# Sheet3.net
KiCad netlist of a schematic drawn in Altium Designer
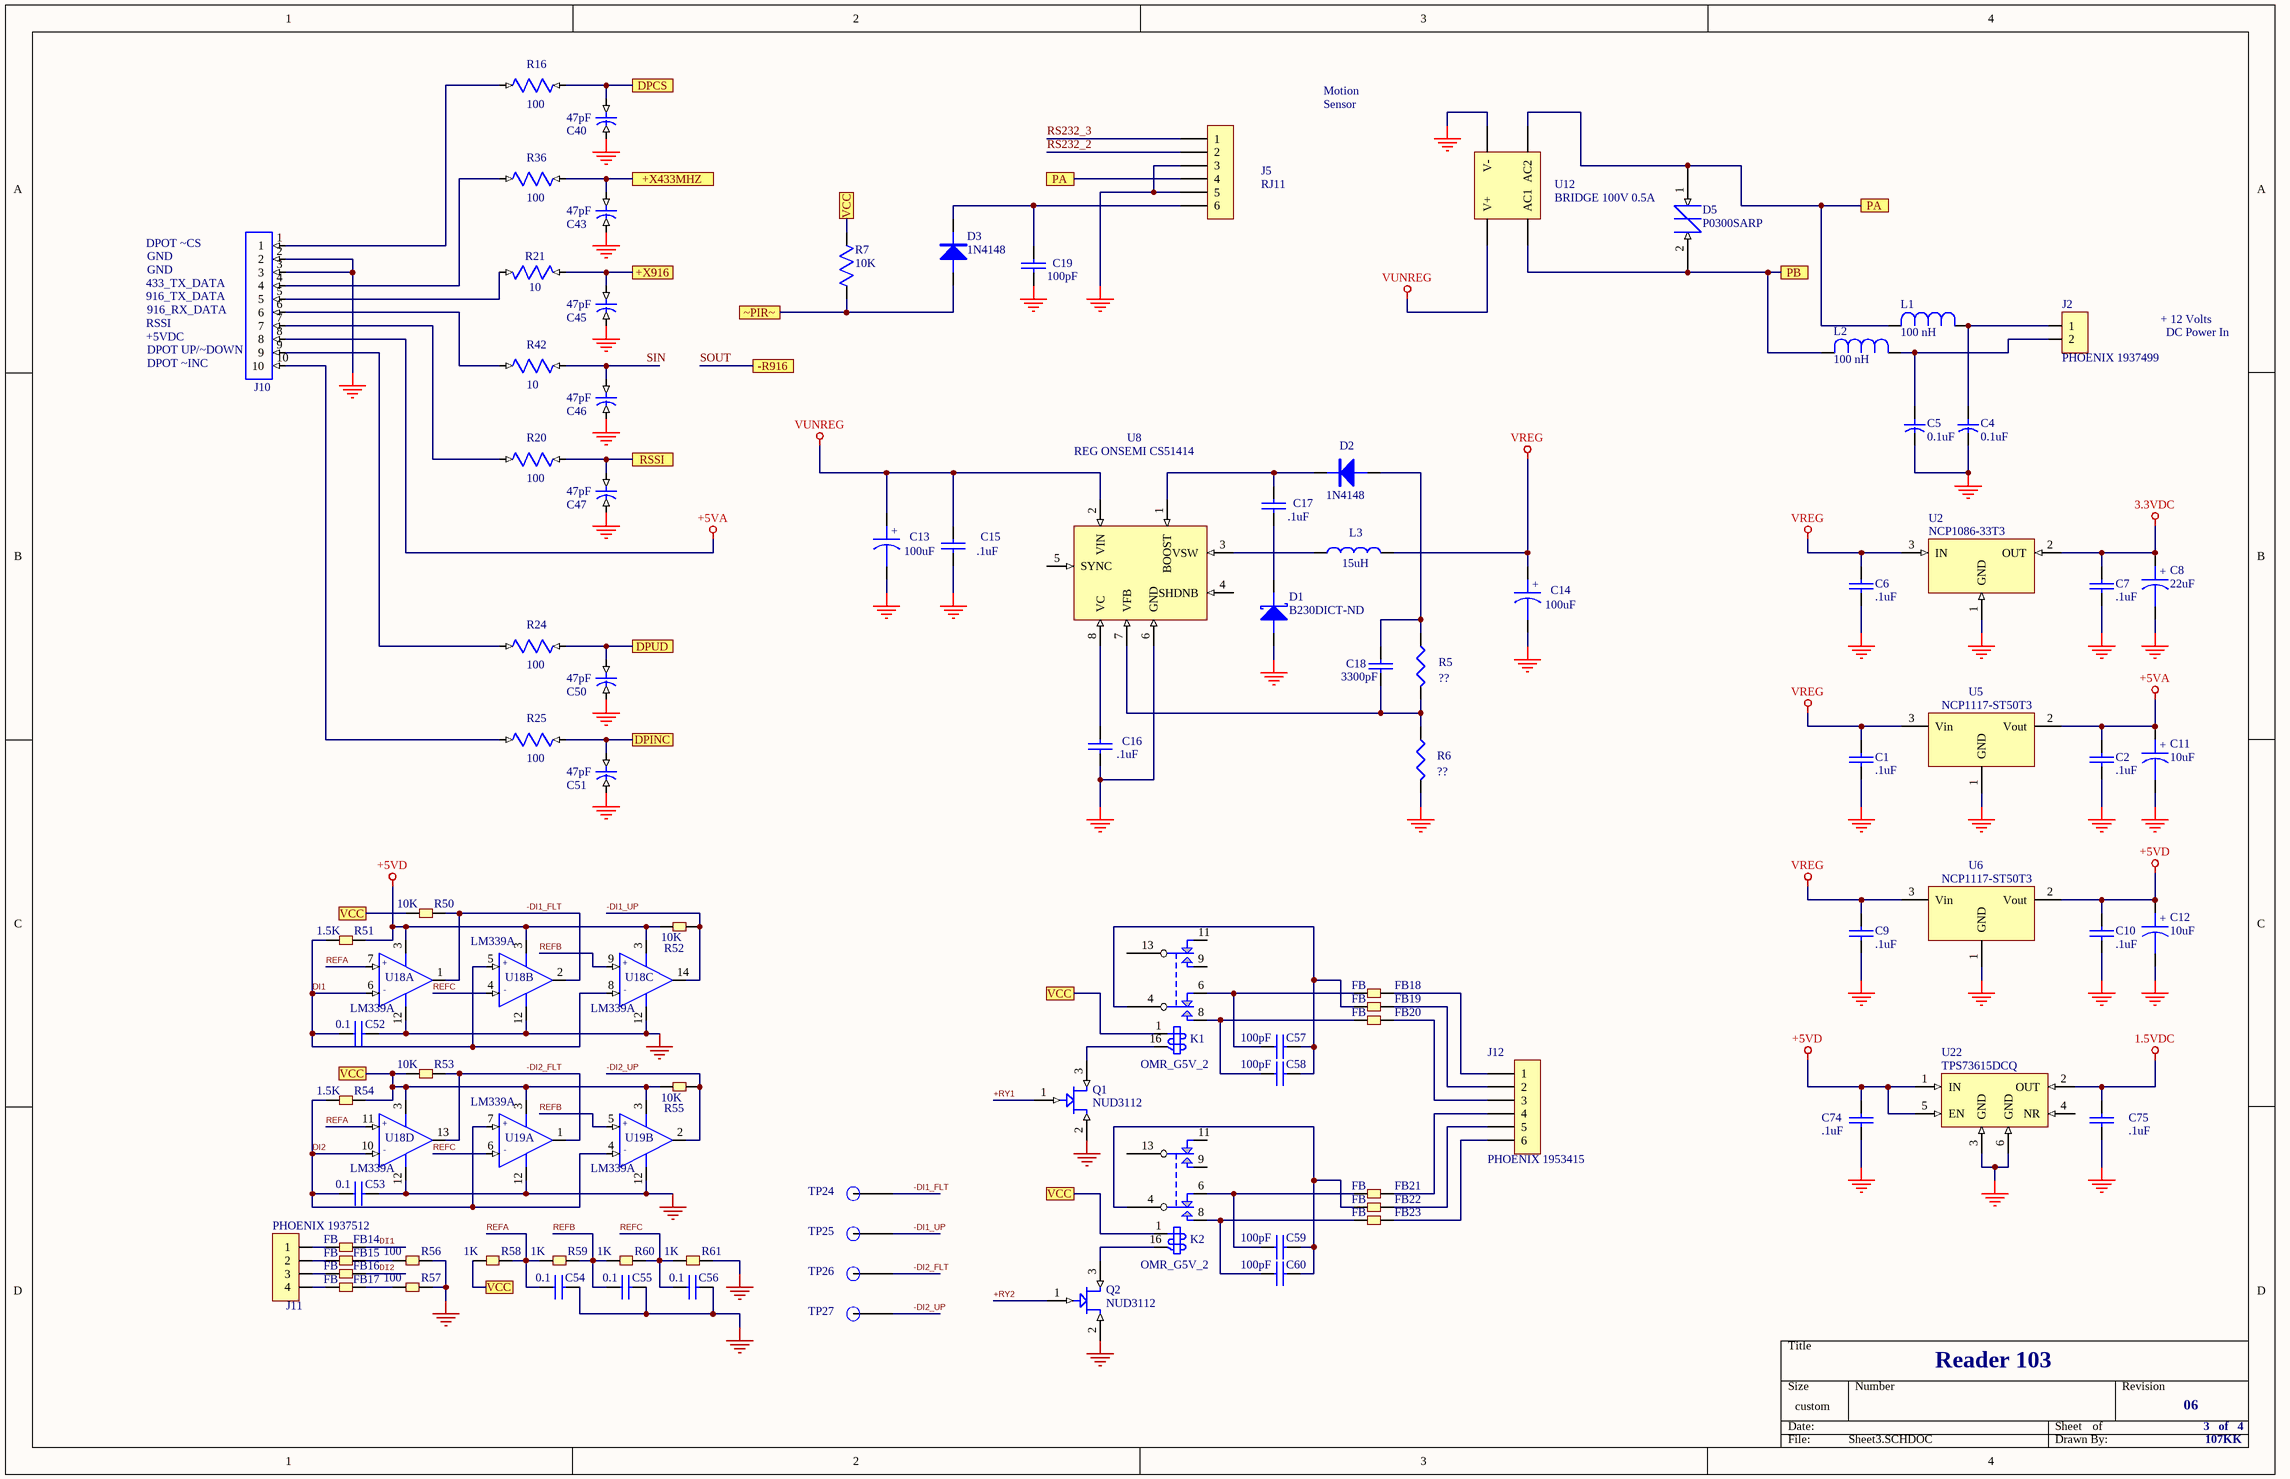
[diagram p0: Sheet3.SCHDOC]

(export (version "E")
  (design (tool "Eeschema 10.0.6"))
  (components
    (comp (ref "C1")
      (value ".1uF")
      (footprint "0603")
      (description "Capacitor")
      (libsource (lib "*") (part "CAP"))
    )
    (comp (ref "C2")
      (value ".1uF")
      (footprint "0603")
      (description "Capacitor")
      (libsource (lib "*") (part "CAP"))
    )
    (comp (ref "C4") (value "0.1uF") (footprint "0603") (libsource (lib "*") (part "C_0603")))
    (comp (ref "C5") (value "0.1uF") (footprint "0603") (libsource (lib "*") (part "C_0603")))
    (comp (ref "C6")
      (value ".1uF")
      (footprint "0603")
      (description "Capacitor")
      (libsource (lib "*") (part "CAP"))
    )
    (comp (ref "C7")
      (value ".1uF")
      (footprint "0603")
      (description "Capacitor")
      (libsource (lib "*") (part "CAP"))
    )
    (comp (ref "C8")
      (value "22uF")
      (footprint "CAP A CASE")
      (description "Capacitor")
      (libsource (lib "*") (part "CAPACITOR POL"))
    )
    (comp (ref "C9")
      (value ".1uF")
      (footprint "0603")
      (description "Capacitor")
      (libsource (lib "*") (part "CAP"))
    )
    (comp (ref "C10")
      (value ".1uF")
      (footprint "0603")
      (description "Capacitor")
      (libsource (lib "*") (part "CAP"))
    )
    (comp (ref "C11")
      (value "10uF")
      (footprint "CAP A CASE")
      (description "Capacitor")
      (libsource (lib "*") (part "CAPACITOR POL"))
    )
    (comp (ref "C12")
      (value "10uF")
      (footprint "CAP A CASE")
      (description "Capacitor")
      (libsource (lib "*") (part "CAPACITOR POL"))
    )
    (comp (ref "C13")
      (value "100uF")
      (footprint "CAP D CASE")
      (description "Capacitor")
      (libsource (lib "*") (part "CAPACITOR POL"))
    )
    (comp (ref "C14")
      (value "100uF")
      (footprint "CAP D CASE")
      (description "Capacitor")
      (libsource (lib "*") (part "CAPACITOR POL"))
    )
    (comp (ref "C15")
      (value ".1uF")
      (footprint "0603")
      (description "Capacitor")
      (libsource (lib "*") (part "CAP"))
    )
    (comp (ref "C16")
      (value ".1uF")
      (footprint "0603")
      (description "Capacitor")
      (libsource (lib "*") (part "CAP"))
    )
    (comp (ref "C17")
      (value ".1uF")
      (footprint "0603")
      (description "Capacitor")
      (libsource (lib "*") (part "CAP"))
    )
    (comp (ref "C18")
      (value "3300pF")
      (footprint "0603")
      (description "Capacitor")
      (libsource (lib "*") (part "CAP"))
    )
    (comp (ref "C19")
      (value "100pF")
      (footprint "0603")
      (description "Capacitor")
      (libsource (lib "*") (part "CAP"))
    )
    (comp (ref "C40") (value "47pF") (footprint "C0603") (libsource (lib "*") (part "C0603")))
    (comp (ref "C43") (value "47pF") (footprint "C0603") (libsource (lib "*") (part "C0603")))
    (comp (ref "C45") (value "47pF") (footprint "C0603") (libsource (lib "*") (part "C0603")))
    (comp (ref "C46") (value "47pF") (footprint "C0603") (libsource (lib "*") (part "C0603")))
    (comp (ref "C47") (value "47pF") (footprint "C0603") (libsource (lib "*") (part "C0603")))
    (comp (ref "C50") (value "47pF") (footprint "C0603") (libsource (lib "*") (part "C0603")))
    (comp (ref "C51") (value "47pF") (footprint "C0603") (libsource (lib "*") (part "C0603")))
    (comp (ref "C52") (value "0.1") (footprint "0805") (libsource (lib "*") (part "CAP NP_1")))
    (comp (ref "C53") (value "0.1") (footprint "0805") (libsource (lib "*") (part "CAP NP_1")))
    (comp (ref "C54") (value "0.1") (footprint "0805") (libsource (lib "*") (part "CAP NP_1")))
    (comp (ref "C55") (value "0.1") (footprint "0805") (libsource (lib "*") (part "CAP NP_1")))
    (comp (ref "C56") (value "0.1") (footprint "0805") (libsource (lib "*") (part "CAP NP_1")))
    (comp (ref "C57") (value "100pF") (footprint "SM/C_0805") (libsource (lib "*") (part "CAP NP_1")))
    (comp (ref "C58") (value "100pF") (footprint "SM/C_0805") (libsource (lib "*") (part "CAP NP_1")))
    (comp (ref "C59") (value "100pF") (footprint "SM/C_0805") (libsource (lib "*") (part "CAP NP_1")))
    (comp (ref "C60") (value "100pF") (footprint "SM/C_0805") (libsource (lib "*") (part "CAP NP_1")))
    (comp (ref "C74")
      (value ".1uF")
      (footprint "0603")
      (description "Capacitor")
      (libsource (lib "*") (part "CAP"))
    )
    (comp (ref "C75")
      (value ".1uF")
      (footprint "0603")
      (description "Capacitor")
      (libsource (lib "*") (part "CAP"))
    )
    (comp (ref "D1")
      (value "B230DICT-ND")
      (footprint "DIODE SMB")
      (description "Schottky Diode")
      (libsource (lib "*") (part "DIODE SCHOTTKY"))
    )
    (comp (ref "D2")
      (value "1N4148")
      (footprint "SOD123")
      (description "Diode")
      (libsource (lib "*") (part "DIODE"))
    )
    (comp (ref "D3")
      (value "1N4148")
      (footprint "SOD123")
      (description "Diode")
      (libsource (lib "*") (part "DIODE"))
    )
    (comp (ref "D5") (value "P0300SARP") (footprint "TRANSORB_1") (libsource (lib "*") (part "TRANSORB")))
    (comp (ref "FB14") (value "FB") (footprint "0603") (libsource (lib "*") (part "FB")))
    (comp (ref "FB15") (value "FB") (footprint "0603") (libsource (lib "*") (part "FB")))
    (comp (ref "FB16") (value "FB") (footprint "0603") (libsource (lib "*") (part "FB")))
    (comp (ref "FB17") (value "FB") (footprint "0603") (libsource (lib "*") (part "FB")))
    (comp (ref "FB18") (value "FB") (footprint "SM/R_1206") (libsource (lib "*") (part "FB")))
    (comp (ref "FB19") (value "FB") (footprint "SM/R_1206") (libsource (lib "*") (part "FB")))
    (comp (ref "FB20") (value "FB") (footprint "SM/R_1206") (libsource (lib "*") (part "FB")))
    (comp (ref "FB21") (value "FB") (footprint "SM/R_1206") (libsource (lib "*") (part "FB")))
    (comp (ref "FB22") (value "FB") (footprint "SM/R_1206") (libsource (lib "*") (part "FB")))
    (comp (ref "FB23") (value "FB") (footprint "SM/R_1206") (libsource (lib "*") (part "FB")))
    (comp (ref "J2")
      (value "PHOENIX 1937499")
      (footprint "CONN PHOENIX 1803227-2")
      (description "Connector")
      (libsource (lib "*") (part "CON2"))
    )
    (comp (ref "J5")
      (value "RJ11")
      (footprint "RJ11")
      (description "Connector")
      (libsource (lib "*") (part "CON6"))
    )
    (comp (ref "J10") (value "1X10 HEADER") (footprint "1X10 HEADER") (libsource (lib "*") (part "HDR10")))
    (comp (ref "J11")
      (value "PHOENIX 1937512")
      (footprint "CONN PHOENIX 1803293-4")
      (libsource (lib "*") (part "CON4"))
    )
    (comp (ref "J12")
      (value "PHOENIX 1953415")
      (footprint "CONN PHOENIX 1953211-6")
      (description "Connector")
      (libsource (lib "*") (part "CON6"))
    )
    (comp (ref "K1") (value "OMR_G5V_2") (footprint "RELAY44") (libsource (lib "*") (part "OMRON_G5V_3")))
    (comp (ref "K2") (value "OMR_G5V_2") (footprint "RELAY44") (libsource (lib "*") (part "OMRON_G5V_3")))
    (comp (ref "L1") (value "100 nH") (footprint "0603") (libsource (lib "*") (part "INDUCTOR_1")))
    (comp (ref "L2") (value "100 nH") (footprint "0603") (libsource (lib "*") (part "INDUCTOR_1")))
    (comp (ref "L3")
      (value "15uH")
      (footprint "COIL COILTRONICS UP2B-150")
      (libsource (lib "*") (part "INDUCTOR1"))
    )
    (comp (ref "Q1")
      (value "NUD3112")
      (footprint "SOT23")
      (libsource (lib "*") (part "INDUCTIVE LOAD DRIVER"))
    )
    (comp (ref "Q2")
      (value "NUD3112")
      (footprint "SOT23")
      (libsource (lib "*") (part "INDUCTIVE LOAD DRIVER"))
    )
    (comp (ref "R5") (value "??") (footprint "0603") (libsource (lib "*") (part "RES1")))
    (comp (ref "R6") (value "??") (footprint "0603") (libsource (lib "*") (part "RES1")))
    (comp (ref "R7") (value "10K") (footprint "0603") (libsource (lib "*") (part "R_0603")))
    (comp (ref "R16") (value "100") (footprint "R0603") (libsource (lib "*") (part "R0603")))
    (comp (ref "R20") (value "100") (footprint "R0603") (libsource (lib "*") (part "R0603")))
    (comp (ref "R21") (value "10") (footprint "R-603") (libsource (lib "*") (part "R_603")))
    (comp (ref "R24") (value "100") (footprint "R0603") (libsource (lib "*") (part "R0603")))
    (comp (ref "R25") (value "100") (footprint "R0603") (libsource (lib "*") (part "R0603")))
    (comp (ref "R36") (value "100") (footprint "R0603") (libsource (lib "*") (part "R0603")))
    (comp (ref "R42") (value "10") (footprint "R0603") (libsource (lib "*") (part "R0603")))
    (comp (ref "R50") (value "10K") (footprint "0805") (libsource (lib "*") (part "RS")))
    (comp (ref "R51") (value "1.5K") (footprint "0805") (libsource (lib "*") (part "RS")))
    (comp (ref "R52") (value "10K") (footprint "0805") (libsource (lib "*") (part "RS")))
    (comp (ref "R53") (value "10K") (footprint "0805") (libsource (lib "*") (part "RS")))
    (comp (ref "R54") (value "1.5K") (footprint "0805") (libsource (lib "*") (part "RS")))
    (comp (ref "R55") (value "10K") (footprint "0805") (libsource (lib "*") (part "RS")))
    (comp (ref "R56") (value "100") (footprint "0805") (libsource (lib "*") (part "RS")))
    (comp (ref "R57") (value "100") (footprint "0805") (libsource (lib "*") (part "RS")))
    (comp (ref "R58") (value "1K") (footprint "0805") (libsource (lib "*") (part "RS")))
    (comp (ref "R59") (value "1K") (footprint "0805") (libsource (lib "*") (part "RS")))
    (comp (ref "R60") (value "1K") (footprint "0805") (libsource (lib "*") (part "RS")))
    (comp (ref "R61") (value "1K") (footprint "0805") (libsource (lib "*") (part "RS")))
    (comp (ref "TP24") (value "TP") (footprint "TESTPOINT-1") (libsource (lib "*") (part "TESTPOINT_1")))
    (comp (ref "TP25") (value "TP") (footprint "TESTPOINT-1") (libsource (lib "*") (part "TESTPOINT_1")))
    (comp (ref "TP26") (value "TP") (footprint "TESTPOINT-1") (libsource (lib "*") (part "TESTPOINT_1")))
    (comp (ref "TP27") (value "TP") (footprint "TESTPOINT-1") (libsource (lib "*") (part "TESTPOINT_1")))
    (comp (ref "U2")
      (value "NCP1086-33T3")
      (footprint "SOT223 REG GOI")
      (libsource (lib "*") (part "REG GOI"))
    )
    (comp (ref "U5")
      (value "NCP1117-ST50T3")
      (footprint "SOT223 REG")
      (libsource (lib "*") (part "REG REVERSED"))
    )
    (comp (ref "U6")
      (value "NCP1117-ST50T3")
      (footprint "SOT223 REG")
      (libsource (lib "*") (part "REG REVERSED"))
    )
    (comp (ref "U8")
      (value "REG ONSEMI CS51414")
      (footprint "SO8")
      (libsource (lib "*") (part "REG ONSEMI CS51414"))
    )
    (comp (ref "U12")
      (value "BRIDGE 100V 0.5A")
      (footprint "BRIDGE")
      (description "Diode Bridge")
      (libsource (lib "*") (part "BRIDGE2"))
    )
    (comp (ref "U18") (value "LM339A") (footprint "SO14") (libsource (lib "*") (part "LM339")))
    (comp (ref "U19") (value "LM339A") (footprint "SO14") (libsource (lib "*") (part "LM339")))
    (comp (ref "U22")
      (value "TPS73615DCQ")
      (footprint "SOT223-5")
      (libsource (lib "*") (part "REG SOT223-5"))
    )
  )
  (nets
    (net (code "1") (name "+5VA") (class "Default")
      (node (ref "C11") (pin "1") (pinfunction "1_1") (pintype "passive"))
      (node (ref "C2") (pin "1") (pinfunction "1_1") (pintype "passive"))
      (node (ref "J10") (pin "8") (pinfunction "8_8") (pintype "input"))
      (node (ref "U5") (pin "2") (pinfunction "Vout_2") (pintype "passive"))
    )
    (net (code "2") (name "+5VD") (class "Default")
      (node (ref "C10") (pin "1") (pinfunction "1_1") (pintype "passive"))
      (node (ref "C12") (pin "1") (pinfunction "1_1") (pintype "passive"))
      (node (ref "C74") (pin "1") (pinfunction "1_1") (pintype "passive"))
      (node (ref "R51") (pin "1") (pinfunction "1_1") (pintype "passive"))
      (node (ref "R52") (pin "2") (pinfunction "2_2") (pintype "passive"))
      (node (ref "U18") (pin "3") (pinfunction "V+_3") (pintype "power_in"))
      (node (ref "U22") (pin "1") (pinfunction "IN_1") (pintype "input"))
      (node (ref "U22") (pin "5") (pinfunction "EN_5") (pintype "input"))
      (node (ref "U6") (pin "2") (pinfunction "Vout_2") (pintype "passive"))
    )
    (net (code "3") (name "/+RY1") (class "Default")
      (node (ref "Q1") (pin "1") (pinfunction "G_1") (pintype "input"))
    )
    (net (code "4") (name "/+RY2") (class "Default")
      (node (ref "Q2") (pin "1") (pinfunction "G_1") (pintype "input"))
    )
    (net (code "5") (name "/+X433MHZ") (class "Default")
      (node (ref "C43") (pin "1") (pinfunction "A_1") (pintype "input"))
      (node (ref "R36") (pin "2") (pinfunction "B_2") (pintype "input"))
    )
    (net (code "6") (name "/+X916") (class "Default")
      (node (ref "C45") (pin "1") (pinfunction "A_1") (pintype "input"))
      (node (ref "R21") (pin "1") (pinfunction "A_1") (pintype "input"))
    )
    (net (code "7") (name "/-DI1_FLT") (class "Default")
      (node (ref "R50") (pin "1") (pinfunction "1_1") (pintype "passive"))
      (node (ref "TP24") (pin "1") (pinfunction "TP_1") (pintype "passive"))
      (node (ref "U18") (pin "1") (pinfunction "OUT_1") (pintype "open_collector"))
      (node (ref "U18") (pin "2") (pinfunction "OUT_2") (pintype "open_collector"))
    )
    (net (code "8") (name "/-DI1_UP") (class "Default")
      (node (ref "R52") (pin "1") (pinfunction "1_1") (pintype "passive"))
      (node (ref "TP25") (pin "1") (pinfunction "TP_1") (pintype "passive"))
      (node (ref "U18") (pin "14") (pinfunction "OUT_14") (pintype "open_collector"))
    )
    (net (code "9") (name "/-DI2_FLT") (class "Default")
      (node (ref "R53") (pin "1") (pinfunction "1_1") (pintype "passive"))
      (node (ref "TP26") (pin "1") (pinfunction "TP_1") (pintype "passive"))
      (node (ref "U18") (pin "13") (pinfunction "OUT_13") (pintype "open_collector"))
      (node (ref "U19") (pin "1") (pinfunction "OUT_1") (pintype "open_collector"))
    )
    (net (code "10") (name "/-DI2_UP") (class "Default")
      (node (ref "R55") (pin "1") (pinfunction "1_1") (pintype "passive"))
      (node (ref "TP27") (pin "1") (pinfunction "TP_1") (pintype "passive"))
      (node (ref "U19") (pin "2") (pinfunction "OUT_2") (pintype "open_collector"))
    )
    (net (code "11") (name "/DI1") (class "Default")
      (node (ref "C52") (pin "1") (pinfunction "1_1") (pintype "passive"))
      (node (ref "FB14") (pin "1") (pinfunction "1_1") (pintype "passive"))
      (node (ref "R51") (pin "2") (pinfunction "2_2") (pintype "passive"))
      (node (ref "U18") (pin "5") (pinfunction "+_5") (pintype "input"))
      (node (ref "U18") (pin "6") (pinfunction "-_6") (pintype "input"))
      (node (ref "U18") (pin "8") (pinfunction "-_8") (pintype "input"))
    )
    (net (code "12") (name "/DI2") (class "Default")
      (node (ref "C53") (pin "1") (pinfunction "1_1") (pintype "passive"))
      (node (ref "FB16") (pin "1") (pinfunction "1_1") (pintype "passive"))
      (node (ref "R54") (pin "2") (pinfunction "2_2") (pintype "passive"))
      (node (ref "U18") (pin "10") (pinfunction "-_10") (pintype "input"))
      (node (ref "U19") (pin "4") (pinfunction "-_4") (pintype "input"))
      (node (ref "U19") (pin "7") (pinfunction "+_7") (pintype "input"))
    )
    (net (code "13") (name "/DPCS") (class "Default")
      (node (ref "C40") (pin "1") (pinfunction "A_1") (pintype "input"))
      (node (ref "R16") (pin "2") (pinfunction "B_2") (pintype "input"))
    )
    (net (code "14") (name "/DPINC") (class "Default")
      (node (ref "C51") (pin "1") (pinfunction "A_1") (pintype "input"))
      (node (ref "R25") (pin "2") (pinfunction "B_2") (pintype "input"))
    )
    (net (code "15") (name "/DPUD") (class "Default")
      (node (ref "C50") (pin "1") (pinfunction "A_1") (pintype "input"))
      (node (ref "R24") (pin "2") (pinfunction "B_2") (pintype "input"))
    )
    (net (code "16") (name "/PA") (class "Default")
      (node (ref "D5") (pin "1") (pinfunction "1_1") (pintype "input"))
      (node (ref "J5") (pin "4") (pinfunction "4_4") (pintype "passive"))
      (node (ref "L1") (pin "1") (pinfunction "B_1") (pintype "passive"))
      (node (ref "U12") (pin "AC2") (pinfunction "AC2_AC2") (pintype "passive"))
    )
    (net (code "17") (name "/PB") (class "Default")
      (node (ref "D5") (pin "2") (pinfunction "2_2") (pintype "input"))
      (node (ref "L2") (pin "1") (pinfunction "B_1") (pintype "passive"))
      (node (ref "U12") (pin "AC1") (pinfunction "AC1_AC1") (pintype "passive"))
    )
    (net (code "18") (name "/REFA") (class "Default")
      (node (ref "C54") (pin "1") (pinfunction "1_1") (pintype "passive"))
      (node (ref "R58") (pin "1") (pinfunction "1_1") (pintype "passive"))
      (node (ref "R59") (pin "2") (pinfunction "2_2") (pintype "passive"))
      (node (ref "U18") (pin "11") (pinfunction "+_11") (pintype "input"))
      (node (ref "U18") (pin "7") (pinfunction "+_7") (pintype "input"))
    )
    (net (code "19") (name "/REFB") (class "Default")
      (node (ref "C55") (pin "1") (pinfunction "1_1") (pintype "passive"))
      (node (ref "R59") (pin "1") (pinfunction "1_1") (pintype "passive"))
      (node (ref "R60") (pin "2") (pinfunction "2_2") (pintype "passive"))
      (node (ref "U18") (pin "9") (pinfunction "+_9") (pintype "input"))
      (node (ref "U19") (pin "5") (pinfunction "+_5") (pintype "input"))
    )
    (net (code "20") (name "/REFC") (class "Default")
      (node (ref "C56") (pin "1") (pinfunction "1_1") (pintype "passive"))
      (node (ref "R60") (pin "1") (pinfunction "1_1") (pintype "passive"))
      (node (ref "R61") (pin "2") (pinfunction "2_2") (pintype "passive"))
      (node (ref "U18") (pin "4") (pinfunction "-_4") (pintype "input"))
      (node (ref "U19") (pin "6") (pinfunction "-_6") (pintype "input"))
    )
    (net (code "21") (name "/RS232_2") (class "Default")
      (node (ref "J5") (pin "2") (pinfunction "2_2") (pintype "passive"))
    )
    (net (code "22") (name "/RS232_3") (class "Default")
      (node (ref "J5") (pin "1") (pinfunction "1_1") (pintype "passive"))
    )
    (net (code "23") (name "/RSSI") (class "Default")
      (node (ref "C47") (pin "1") (pinfunction "A_1") (pintype "input"))
      (node (ref "R20") (pin "2") (pinfunction "B_2") (pintype "input"))
    )
    (net (code "24") (name "/SIN") (class "Default")
      (node (ref "C46") (pin "1") (pinfunction "A_1") (pintype "input"))
      (node (ref "R42") (pin "2") (pinfunction "B_2") (pintype "input"))
    )
    (net (code "26") (name "/VCC") (class "Default")
      (node (ref "K1") (pin "1") (pinfunction "COIL1_1") (pintype "passive"))
      (node (ref "K2") (pin "1") (pinfunction "COIL1_1") (pintype "passive"))
      (node (ref "R50") (pin "2") (pinfunction "2_2") (pintype "passive"))
      (node (ref "R53") (pin "2") (pinfunction "2_2") (pintype "passive"))
      (node (ref "R54") (pin "1") (pinfunction "1_1") (pintype "passive"))
      (node (ref "R55") (pin "2") (pinfunction "2_2") (pintype "passive"))
      (node (ref "R58") (pin "2") (pinfunction "2_2") (pintype "passive"))
      (node (ref "R7") (pin "1") (pinfunction "A_1") (pintype "passive"))
      (node (ref "U18") (pin "3") (pinfunction "V+_3") (pintype "power_in"))
      (node (ref "U19") (pin "3") (pinfunction "V+_3") (pintype "power_in"))
    )
    (net (code "27") (name "/~PIR~") (class "Default")
      (node (ref "D3") (pin "A") (pinfunction "A_A") (pintype "passive"))
      (node (ref "R7") (pin "2") (pinfunction "B_2") (pintype "passive"))
    )
    (net (code "28") (name "1.5VDC") (class "Default")
      (node (ref "C75") (pin "1") (pinfunction "1_1") (pintype "passive"))
      (node (ref "U22") (pin "2") (pinfunction "OUT_2") (pintype "input"))
    )
    (net (code "29") (name "3.3VDC") (class "Default")
      (node (ref "C7") (pin "1") (pinfunction "1_1") (pintype "passive"))
      (node (ref "C8") (pin "1") (pinfunction "1_1") (pintype "passive"))
      (node (ref "U2") (pin "2") (pinfunction "OUT_2") (pintype "input"))
    )
    (net (code "30") (name "GND_COM") (class "Default")
      (node (ref "C1") (pin "2") (pinfunction "2_2") (pintype "passive"))
      (node (ref "C10") (pin "2") (pinfunction "2_2") (pintype "passive"))
      (node (ref "C11") (pin "2") (pinfunction "2_2") (pintype "passive"))
      (node (ref "C12") (pin "2") (pinfunction "2_2") (pintype "passive"))
      (node (ref "C13") (pin "2") (pinfunction "2_2") (pintype "passive"))
      (node (ref "C14") (pin "2") (pinfunction "2_2") (pintype "passive"))
      (node (ref "C15") (pin "2") (pinfunction "2_2") (pintype "passive"))
      (node (ref "C16") (pin "2") (pinfunction "2_2") (pintype "passive"))
      (node (ref "C19") (pin "2") (pinfunction "2_2") (pintype "passive"))
      (node (ref "C2") (pin "2") (pinfunction "2_2") (pintype "passive"))
      (node (ref "C4") (pin "2") (pinfunction "B_2") (pintype "passive"))
      (node (ref "C40") (pin "2") (pinfunction "B_2") (pintype "input"))
      (node (ref "C43") (pin "2") (pinfunction "B_2") (pintype "input"))
      (node (ref "C45") (pin "2") (pinfunction "B_2") (pintype "input"))
      (node (ref "C46") (pin "2") (pinfunction "B_2") (pintype "input"))
      (node (ref "C47") (pin "2") (pinfunction "B_2") (pintype "input"))
      (node (ref "C5") (pin "2") (pinfunction "B_2") (pintype "passive"))
      (node (ref "C50") (pin "2") (pinfunction "B_2") (pintype "input"))
      (node (ref "C51") (pin "2") (pinfunction "B_2") (pintype "input"))
      (node (ref "C52") (pin "2") (pinfunction "2_2") (pintype "passive"))
      (node (ref "C53") (pin "2") (pinfunction "2_2") (pintype "passive"))
      (node (ref "C54") (pin "2") (pinfunction "2_2") (pintype "passive"))
      (node (ref "C55") (pin "2") (pinfunction "2_2") (pintype "passive"))
      (node (ref "C56") (pin "2") (pinfunction "2_2") (pintype "passive"))
      (node (ref "C6") (pin "2") (pinfunction "2_2") (pintype "passive"))
      (node (ref "C7") (pin "2") (pinfunction "2_2") (pintype "passive"))
      (node (ref "C74") (pin "2") (pinfunction "2_2") (pintype "passive"))
      (node (ref "C75") (pin "2") (pinfunction "2_2") (pintype "passive"))
      (node (ref "C8") (pin "2") (pinfunction "2_2") (pintype "passive"))
      (node (ref "C9") (pin "2") (pinfunction "2_2") (pintype "passive"))
      (node (ref "D1") (pin "A") (pinfunction "A_A") (pintype "passive"))
      (node (ref "J10") (pin "2") (pinfunction "2_2") (pintype "input"))
      (node (ref "J10") (pin "3") (pinfunction "3_3") (pintype "input"))
      (node (ref "J5") (pin "3") (pinfunction "3_3") (pintype "passive"))
      (node (ref "J5") (pin "5") (pinfunction "5_5") (pintype "passive"))
      (node (ref "Q1") (pin "2") (pinfunction "S_2") (pintype "input"))
      (node (ref "Q2") (pin "2") (pinfunction "S_2") (pintype "input"))
      (node (ref "R56") (pin "1") (pinfunction "1_1") (pintype "passive"))
      (node (ref "R57") (pin "1") (pinfunction "1_1") (pintype "passive"))
      (node (ref "R6") (pin "2") (pinfunction "2_2") (pintype "passive"))
      (node (ref "R61") (pin "1") (pinfunction "1_1") (pintype "passive"))
      (node (ref "U12") (pin "V-") (pinfunction "V-_V-") (pintype "passive"))
      (node (ref "U18") (pin "12") (pinfunction "V-_12") (pintype "power_in"))
      (node (ref "U19") (pin "12") (pinfunction "V-_12") (pintype "power_in"))
      (node (ref "U2") (pin "1") (pinfunction "GND_1") (pintype "input"))
      (node (ref "U22") (pin "3") (pinfunction "GND_3") (pintype "input"))
      (node (ref "U22") (pin "6") (pinfunction "GND_6") (pintype "input"))
      (node (ref "U5") (pin "1") (pinfunction "GND_1") (pintype "passive"))
      (node (ref "U6") (pin "1") (pinfunction "GND_1") (pintype "passive"))
      (node (ref "U8") (pin "6") (pinfunction "GND_6") (pintype "input"))
    )
    (net (code "31") (name "Net-(C4-A)") (class "Default")
      (node (ref "C4") (pin "1") (pinfunction "A_1") (pintype "passive"))
      (node (ref "J2") (pin "1") (pinfunction "1_1") (pintype "passive"))
      (node (ref "L1") (pin "2") (pinfunction "A_2") (pintype "passive"))
    )
    (net (code "32") (name "Net-(C5-A)") (class "Default")
      (node (ref "C5") (pin "1") (pinfunction "A_1") (pintype "passive"))
      (node (ref "J2") (pin "2") (pinfunction "2_2") (pintype "passive"))
      (node (ref "L2") (pin "2") (pinfunction "A_2") (pintype "passive"))
    )
    (net (code "33") (name "Net-(C17-Pad2)") (class "Default")
      (node (ref "C17") (pin "2") (pinfunction "2_2") (pintype "passive"))
      (node (ref "D1") (pin "K") (pinfunction "K_K") (pintype "passive"))
    )
    (net (code "34") (name "Net-(C18-Pad1)") (class "Default")
      (node (ref "C18") (pin "1") (pinfunction "1_1") (pintype "passive"))
      (node (ref "D2") (pin "A") (pinfunction "A_A") (pintype "passive"))
      (node (ref "R5") (pin "1") (pinfunction "1_1") (pintype "passive"))
    )
    (net (code "35") (name "Net-(C19-Pad1)") (class "Default")
      (node (ref "C19") (pin "1") (pinfunction "1_1") (pintype "passive"))
      (node (ref "D3") (pin "K") (pinfunction "K_K") (pintype "passive"))
      (node (ref "J5") (pin "6") (pinfunction "6_6") (pintype "passive"))
    )
    (net (code "36") (name "Net-(FB14-Pad2)") (class "Default")
      (node (ref "FB14") (pin "2") (pinfunction "2_2") (pintype "passive"))
      (node (ref "J11") (pin "1") (pinfunction "1_1") (pintype "passive"))
    )
    (net (code "37") (name "Net-(FB15-Pad1)") (class "Default")
      (node (ref "FB15") (pin "1") (pinfunction "1_1") (pintype "passive"))
      (node (ref "R56") (pin "2") (pinfunction "2_2") (pintype "passive"))
    )
    (net (code "38") (name "Net-(FB15-Pad2)") (class "Default")
      (node (ref "FB15") (pin "2") (pinfunction "2_2") (pintype "passive"))
      (node (ref "J11") (pin "2") (pinfunction "2_2") (pintype "passive"))
    )
    (net (code "39") (name "Net-(FB16-Pad2)") (class "Default")
      (node (ref "FB16") (pin "2") (pinfunction "2_2") (pintype "passive"))
      (node (ref "J11") (pin "3") (pinfunction "3_3") (pintype "passive"))
    )
    (net (code "40") (name "Net-(FB17-Pad1)") (class "Default")
      (node (ref "FB17") (pin "1") (pinfunction "1_1") (pintype "passive"))
      (node (ref "R57") (pin "2") (pinfunction "2_2") (pintype "passive"))
    )
    (net (code "41") (name "Net-(FB17-Pad2)") (class "Default")
      (node (ref "FB17") (pin "2") (pinfunction "2_2") (pintype "passive"))
      (node (ref "J11") (pin "4") (pinfunction "4_4") (pintype "passive"))
    )
    (net (code "42") (name "Net-(FB18-Pad1)") (class "Default")
      (node (ref "FB18") (pin "1") (pinfunction "1_1") (pintype "passive"))
      (node (ref "J12") (pin "1") (pinfunction "1_1") (pintype "passive"))
    )
    (net (code "43") (name "Net-(FB19-Pad1)") (class "Default")
      (node (ref "FB19") (pin "1") (pinfunction "1_1") (pintype "passive"))
      (node (ref "J12") (pin "2") (pinfunction "2_2") (pintype "passive"))
    )
    (net (code "44") (name "Net-(FB20-Pad1)") (class "Default")
      (node (ref "FB20") (pin "1") (pinfunction "1_1") (pintype "passive"))
      (node (ref "J12") (pin "3") (pinfunction "3_3") (pintype "passive"))
    )
    (net (code "45") (name "Net-(FB21-Pad1)") (class "Default")
      (node (ref "FB21") (pin "1") (pinfunction "1_1") (pintype "passive"))
      (node (ref "J12") (pin "4") (pinfunction "4_4") (pintype "passive"))
    )
    (net (code "46") (name "Net-(FB22-Pad1)") (class "Default")
      (node (ref "FB22") (pin "1") (pinfunction "1_1") (pintype "passive"))
      (node (ref "J12") (pin "5") (pinfunction "5_5") (pintype "passive"))
    )
    (net (code "47") (name "Net-(FB23-Pad1)") (class "Default")
      (node (ref "FB23") (pin "1") (pinfunction "1_1") (pintype "passive"))
      (node (ref "J12") (pin "6") (pinfunction "6_6") (pintype "passive"))
    )
    (net (code "48") (name "Net-(K1-COIL2)") (class "Default")
      (node (ref "K1") (pin "16") (pinfunction "COIL2_16") (pintype "passive"))
      (node (ref "Q1") (pin "3") (pinfunction "D_3") (pintype "input"))
    )
    (net (code "49") (name "Net-(K1-COMMON2)") (class "Default")
      (node (ref "C57") (pin "2") (pinfunction "2_2") (pintype "passive"))
      (node (ref "C58") (pin "2") (pinfunction "2_2") (pintype "passive"))
      (node (ref "FB19") (pin "2") (pinfunction "2_2") (pintype "passive"))
      (node (ref "K1") (pin "4") (pinfunction "COMMON2_4") (pintype "passive"))
    )
    (net (code "50") (name "Net-(K1-NC2)") (class "Default")
      (node (ref "C57") (pin "1") (pinfunction "1_1") (pintype "passive"))
      (node (ref "FB18") (pin "2") (pinfunction "2_2") (pintype "passive"))
      (node (ref "K1") (pin "6") (pinfunction "NC2_6") (pintype "passive"))
    )
    (net (code "51") (name "Net-(K1-NO2)") (class "Default")
      (node (ref "C58") (pin "1") (pinfunction "1_1") (pintype "passive"))
      (node (ref "FB20") (pin "2") (pinfunction "2_2") (pintype "passive"))
      (node (ref "K1") (pin "8") (pinfunction "NO2_8") (pintype "passive"))
    )
    (net (code "52") (name "Net-(K2-COIL2)") (class "Default")
      (node (ref "K2") (pin "16") (pinfunction "COIL2_16") (pintype "passive"))
      (node (ref "Q2") (pin "3") (pinfunction "D_3") (pintype "input"))
    )
    (net (code "53") (name "Net-(K2-COMMON2)") (class "Default")
      (node (ref "C59") (pin "2") (pinfunction "2_2") (pintype "passive"))
      (node (ref "C60") (pin "2") (pinfunction "2_2") (pintype "passive"))
      (node (ref "FB22") (pin "2") (pinfunction "2_2") (pintype "passive"))
      (node (ref "K2") (pin "4") (pinfunction "COMMON2_4") (pintype "passive"))
    )
    (net (code "54") (name "Net-(K2-NC2)") (class "Default")
      (node (ref "C59") (pin "1") (pinfunction "1_1") (pintype "passive"))
      (node (ref "FB21") (pin "2") (pinfunction "2_2") (pintype "passive"))
      (node (ref "K2") (pin "6") (pinfunction "NC2_6") (pintype "passive"))
    )
    (net (code "55") (name "Net-(K2-NO2)") (class "Default")
      (node (ref "C60") (pin "1") (pinfunction "1_1") (pintype "passive"))
      (node (ref "FB23") (pin "2") (pinfunction "2_2") (pintype "passive"))
      (node (ref "K2") (pin "8") (pinfunction "NO2_8") (pintype "passive"))
    )
    (net (code "56") (name "Net-(R16-A)") (class "Default")
      (node (ref "J10") (pin "1") (pinfunction "1_1") (pintype "input"))
      (node (ref "R16") (pin "1") (pinfunction "A_1") (pintype "input"))
    )
    (net (code "57") (name "Net-(R20-A)") (class "Default")
      (node (ref "J10") (pin "7") (pinfunction "7_7") (pintype "input"))
      (node (ref "R20") (pin "1") (pinfunction "A_1") (pintype "input"))
    )
    (net (code "58") (name "Net-(R21-B)") (class "Default")
      (node (ref "J10") (pin "5") (pinfunction "5_5") (pintype "input"))
      (node (ref "R21") (pin "2") (pinfunction "B_2") (pintype "input"))
    )
    (net (code "59") (name "Net-(R24-A)") (class "Default")
      (node (ref "J10") (pin "9") (pinfunction "9_9") (pintype "input"))
      (node (ref "R24") (pin "1") (pinfunction "A_1") (pintype "input"))
    )
    (net (code "60") (name "Net-(R25-A)") (class "Default")
      (node (ref "J10") (pin "10") (pinfunction "10_10") (pintype "input"))
      (node (ref "R25") (pin "1") (pinfunction "A_1") (pintype "input"))
    )
    (net (code "61") (name "Net-(R36-A)") (class "Default")
      (node (ref "J10") (pin "4") (pinfunction "4_4") (pintype "input"))
      (node (ref "R36") (pin "1") (pinfunction "A_1") (pintype "input"))
    )
    (net (code "62") (name "Net-(R42-A)") (class "Default")
      (node (ref "J10") (pin "6") (pinfunction "6_6") (pintype "input"))
      (node (ref "R42") (pin "1") (pinfunction "A_1") (pintype "input"))
    )
    (net (code "63") (name "Net-(U8-BOOST)") (class "Default")
      (node (ref "C17") (pin "1") (pinfunction "1_1") (pintype "passive"))
      (node (ref "D2") (pin "K") (pinfunction "K_K") (pintype "passive"))
      (node (ref "U8") (pin "1") (pinfunction "BOOST_1") (pintype "input"))
    )
    (net (code "64") (name "Net-(U8-VC)") (class "Default")
      (node (ref "C16") (pin "1") (pinfunction "1_1") (pintype "passive"))
      (node (ref "U8") (pin "8") (pinfunction "VC_8") (pintype "input"))
    )
    (net (code "65") (name "Net-(U8-VFB)") (class "Default")
      (node (ref "C18") (pin "2") (pinfunction "2_2") (pintype "passive"))
      (node (ref "R5") (pin "2") (pinfunction "2_2") (pintype "passive"))
      (node (ref "R6") (pin "1") (pinfunction "1_1") (pintype "passive"))
      (node (ref "U8") (pin "7") (pinfunction "VFB_7") (pintype "input"))
    )
    (net (code "66") (name "Net-(U8-VSW)") (class "Default")
      (node (ref "L3") (pin "1") (pinfunction "1_1") (pintype "passive"))
      (node (ref "U8") (pin "3") (pinfunction "VSW_3") (pintype "input"))
    )
    (net (code "67") (name "VREG") (class "Default")
      (node (ref "C1") (pin "1") (pinfunction "1_1") (pintype "passive"))
      (node (ref "C14") (pin "1") (pinfunction "1_1") (pintype "passive"))
      (node (ref "C6") (pin "1") (pinfunction "1_1") (pintype "passive"))
      (node (ref "C9") (pin "1") (pinfunction "1_1") (pintype "passive"))
      (node (ref "L3") (pin "2") (pinfunction "2_2") (pintype "passive"))
      (node (ref "U2") (pin "3") (pinfunction "IN_3") (pintype "input"))
      (node (ref "U5") (pin "3") (pinfunction "Vin_3") (pintype "passive"))
      (node (ref "U6") (pin "3") (pinfunction "Vin_3") (pintype "passive"))
    )
    (net (code "68") (name "VUNREG") (class "Default")
      (node (ref "C13") (pin "1") (pinfunction "1_1") (pintype "passive"))
      (node (ref "C15") (pin "1") (pinfunction "1_1") (pintype "passive"))
      (node (ref "U12") (pin "V+") (pinfunction "V+_V+") (pintype "passive"))
      (node (ref "U8") (pin "2") (pinfunction "VIN_2") (pintype "input"))
    )
    (net (code "69") (name "unconnected-(K1-COMMON1-Pad13)") (class "Default")
      (node (ref "K1") (pin "13") (pinfunction "COMMON1_13") (pintype "passive"))
    )
    (net (code "70") (name "unconnected-(K1-NC1-Pad11)") (class "Default")
      (node (ref "K1") (pin "11") (pinfunction "NC1_11") (pintype "passive"))
    )
    (net (code "71") (name "unconnected-(K1-NO1-Pad9)") (class "Default")
      (node (ref "K1") (pin "9") (pinfunction "NO1_9") (pintype "passive"))
    )
    (net (code "72") (name "unconnected-(K2-COMMON1-Pad13)") (class "Default")
      (node (ref "K2") (pin "13") (pinfunction "COMMON1_13") (pintype "passive"))
    )
    (net (code "73") (name "unconnected-(K2-NC1-Pad11)") (class "Default")
      (node (ref "K2") (pin "11") (pinfunction "NC1_11") (pintype "passive"))
    )
    (net (code "74") (name "unconnected-(K2-NO1-Pad9)") (class "Default")
      (node (ref "K2") (pin "9") (pinfunction "NO1_9") (pintype "passive"))
    )
    (net (code "75") (name "unconnected-(U8-SHDNB-Pad4)") (class "Default")
      (node (ref "U8") (pin "4") (pinfunction "SHDNB_4") (pintype "input"))
    )
    (net (code "76") (name "unconnected-(U8-SYNC-Pad5)") (class "Default")
      (node (ref "U8") (pin "5") (pinfunction "SYNC_5") (pintype "input"))
    )
    (net (code "77") (name "unconnected-(U22-NR-Pad4)") (class "Default")
      (node (ref "U22") (pin "4") (pinfunction "NR_4") (pintype "input"))
    )
  )
)
